# Sheet2.net
KiCad netlist of a schematic drawn in Altium Designer
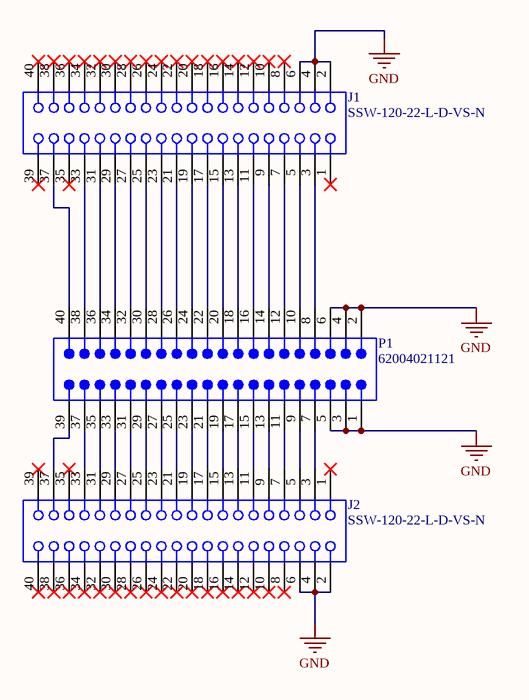
[diagram p0: Sheet2.SchDoc]

(export (version "E")
  (design (tool "Eeschema 10.0.6"))
  (components
    (comp (ref "J1")
      (value "SSW-120-22-L-D-VS-N")
      (footprint "SMTC-SSW-120-22-X-D-VS-N")
      (description "SQ Post Socket, Surface Mount, Vertical, -55 to 125 degC, 2.54 mm Pitch, 40-Pin, Female, RoHS")
      (fields (field (name "MANUFACTURER") "Samtec"))
      (libsource (lib "Altium Content Vault") (part "SMTC-SSW-120-X-X-D"))
    )
    (comp (ref "J2")
      (value "SSW-120-22-L-D-VS-N")
      (footprint "SMTC-SSW-120-22-X-D-VS-N")
      (description "SQ Post Socket, Surface Mount, Vertical, -55 to 125 degC, 2.54 mm Pitch, 40-Pin, Female, RoHS")
      (fields (field (name "MANUFACTURER") "Samtec"))
      (libsource (lib "Altium Content Vault") (part "SMTC-SSW-120-X-X-D"))
    )
    (comp (ref "P1")
      (value "62004021121")
      (footprint "62004021121")
      (description "62004021121 Conn, Header, 40Pos, 2Row, 2Mm Rohs Compliant: Yes")
      (libsource (lib "Altium Content Vault") (part "Header_Male_2R_40P"))
    )
  )
  (nets
    (net (code "1") (name "GND") (class "Default")
      (node (ref "J1") (pin "2") (pinfunction "2_2") (pintype "passive"))
      (node (ref "J1") (pin "4") (pinfunction "4_4") (pintype "passive"))
      (node (ref "J1") (pin "6") (pinfunction "6_6") (pintype "passive"))
      (node (ref "J2") (pin "2") (pinfunction "2_2") (pintype "passive"))
      (node (ref "J2") (pin "4") (pinfunction "4_4") (pintype "passive"))
      (node (ref "J2") (pin "6") (pinfunction "6_6") (pintype "passive"))
      (node (ref "P1") (pin "1") (pinfunction "1_1") (pintype "passive"))
      (node (ref "P1") (pin "2") (pinfunction "2_2") (pintype "passive"))
      (node (ref "P1") (pin "3") (pinfunction "3_3") (pintype "passive"))
      (node (ref "P1") (pin "4") (pinfunction "4_4") (pintype "passive"))
      (node (ref "P1") (pin "5") (pinfunction "5_5") (pintype "passive"))
      (node (ref "P1") (pin "6") (pinfunction "6_6") (pintype "passive"))
    )
    (net (code "2") (name "Net-(J1-Pad3)") (class "Default")
      (node (ref "J1") (pin "3") (pinfunction "3_3") (pintype "passive"))
      (node (ref "P1") (pin "8") (pinfunction "8_8") (pintype "passive"))
    )
    (net (code "3") (name "Net-(J1-Pad5)") (class "Default")
      (node (ref "J1") (pin "5") (pinfunction "5_5") (pintype "passive"))
      (node (ref "P1") (pin "10") (pinfunction "10_10") (pintype "passive"))
    )
    (net (code "4") (name "Net-(J1-Pad7)") (class "Default")
      (node (ref "J1") (pin "7") (pinfunction "7_7") (pintype "passive"))
      (node (ref "P1") (pin "12") (pinfunction "12_12") (pintype "passive"))
    )
    (net (code "5") (name "Net-(J1-Pad9)") (class "Default")
      (node (ref "J1") (pin "9") (pinfunction "9_9") (pintype "passive"))
      (node (ref "P1") (pin "14") (pinfunction "14_14") (pintype "passive"))
    )
    (net (code "6") (name "Net-(J1-Pad11)") (class "Default")
      (node (ref "J1") (pin "11") (pinfunction "11_11") (pintype "passive"))
      (node (ref "P1") (pin "16") (pinfunction "16_16") (pintype "passive"))
    )
    (net (code "7") (name "Net-(J1-Pad13)") (class "Default")
      (node (ref "J1") (pin "13") (pinfunction "13_13") (pintype "passive"))
      (node (ref "P1") (pin "18") (pinfunction "18_18") (pintype "passive"))
    )
    (net (code "8") (name "Net-(J1-Pad15)") (class "Default")
      (node (ref "J1") (pin "15") (pinfunction "15_15") (pintype "passive"))
      (node (ref "P1") (pin "20") (pinfunction "20_20") (pintype "passive"))
    )
    (net (code "9") (name "Net-(J1-Pad17)") (class "Default")
      (node (ref "J1") (pin "17") (pinfunction "17_17") (pintype "passive"))
      (node (ref "P1") (pin "22") (pinfunction "22_22") (pintype "passive"))
    )
    (net (code "10") (name "Net-(J1-Pad19)") (class "Default")
      (node (ref "J1") (pin "19") (pinfunction "19_19") (pintype "passive"))
      (node (ref "P1") (pin "24") (pinfunction "24_24") (pintype "passive"))
    )
    (net (code "11") (name "Net-(J1-Pad21)") (class "Default")
      (node (ref "J1") (pin "21") (pinfunction "21_21") (pintype "passive"))
      (node (ref "P1") (pin "26") (pinfunction "26_26") (pintype "passive"))
    )
    (net (code "12") (name "Net-(J1-Pad23)") (class "Default")
      (node (ref "J1") (pin "23") (pinfunction "23_23") (pintype "passive"))
      (node (ref "P1") (pin "28") (pinfunction "28_28") (pintype "passive"))
    )
    (net (code "13") (name "Net-(J1-Pad25)") (class "Default")
      (node (ref "J1") (pin "25") (pinfunction "25_25") (pintype "passive"))
      (node (ref "P1") (pin "30") (pinfunction "30_30") (pintype "passive"))
    )
    (net (code "14") (name "Net-(J1-Pad27)") (class "Default")
      (node (ref "J1") (pin "27") (pinfunction "27_27") (pintype "passive"))
      (node (ref "P1") (pin "32") (pinfunction "32_32") (pintype "passive"))
    )
    (net (code "15") (name "Net-(J1-Pad29)") (class "Default")
      (node (ref "J1") (pin "29") (pinfunction "29_29") (pintype "passive"))
      (node (ref "P1") (pin "34") (pinfunction "34_34") (pintype "passive"))
    )
    (net (code "16") (name "Net-(J1-Pad31)") (class "Default")
      (node (ref "J1") (pin "31") (pinfunction "31_31") (pintype "passive"))
      (node (ref "P1") (pin "36") (pinfunction "36_36") (pintype "passive"))
    )
    (net (code "17") (name "Net-(J1-Pad33)") (class "Default")
      (node (ref "J1") (pin "33") (pinfunction "33_33") (pintype "passive"))
      (node (ref "P1") (pin "38") (pinfunction "38_38") (pintype "passive"))
    )
    (net (code "18") (name "Net-(J1-Pad37)") (class "Default")
      (node (ref "J1") (pin "37") (pinfunction "37_37") (pintype "passive"))
      (node (ref "P1") (pin "40") (pinfunction "40_40") (pintype "passive"))
    )
    (net (code "19") (name "Net-(J2-Pad3)") (class "Default")
      (node (ref "J2") (pin "3") (pinfunction "3_3") (pintype "passive"))
      (node (ref "P1") (pin "7") (pinfunction "7_7") (pintype "passive"))
    )
    (net (code "20") (name "Net-(J2-Pad5)") (class "Default")
      (node (ref "J2") (pin "5") (pinfunction "5_5") (pintype "passive"))
      (node (ref "P1") (pin "9") (pinfunction "9_9") (pintype "passive"))
    )
    (net (code "21") (name "Net-(J2-Pad7)") (class "Default")
      (node (ref "J2") (pin "7") (pinfunction "7_7") (pintype "passive"))
      (node (ref "P1") (pin "11") (pinfunction "11_11") (pintype "passive"))
    )
    (net (code "22") (name "Net-(J2-Pad9)") (class "Default")
      (node (ref "J2") (pin "9") (pinfunction "9_9") (pintype "passive"))
      (node (ref "P1") (pin "13") (pinfunction "13_13") (pintype "passive"))
    )
    (net (code "23") (name "Net-(J2-Pad11)") (class "Default")
      (node (ref "J2") (pin "11") (pinfunction "11_11") (pintype "passive"))
      (node (ref "P1") (pin "15") (pinfunction "15_15") (pintype "passive"))
    )
    (net (code "24") (name "Net-(J2-Pad13)") (class "Default")
      (node (ref "J2") (pin "13") (pinfunction "13_13") (pintype "passive"))
      (node (ref "P1") (pin "17") (pinfunction "17_17") (pintype "passive"))
    )
    (net (code "25") (name "Net-(J2-Pad15)") (class "Default")
      (node (ref "J2") (pin "15") (pinfunction "15_15") (pintype "passive"))
      (node (ref "P1") (pin "19") (pinfunction "19_19") (pintype "passive"))
    )
    (net (code "26") (name "Net-(J2-Pad17)") (class "Default")
      (node (ref "J2") (pin "17") (pinfunction "17_17") (pintype "passive"))
      (node (ref "P1") (pin "21") (pinfunction "21_21") (pintype "passive"))
    )
    (net (code "27") (name "Net-(J2-Pad19)") (class "Default")
      (node (ref "J2") (pin "19") (pinfunction "19_19") (pintype "passive"))
      (node (ref "P1") (pin "23") (pinfunction "23_23") (pintype "passive"))
    )
    (net (code "28") (name "Net-(J2-Pad21)") (class "Default")
      (node (ref "J2") (pin "21") (pinfunction "21_21") (pintype "passive"))
      (node (ref "P1") (pin "25") (pinfunction "25_25") (pintype "passive"))
    )
    (net (code "29") (name "Net-(J2-Pad23)") (class "Default")
      (node (ref "J2") (pin "23") (pinfunction "23_23") (pintype "passive"))
      (node (ref "P1") (pin "27") (pinfunction "27_27") (pintype "passive"))
    )
    (net (code "30") (name "Net-(J2-Pad25)") (class "Default")
      (node (ref "J2") (pin "25") (pinfunction "25_25") (pintype "passive"))
      (node (ref "P1") (pin "29") (pinfunction "29_29") (pintype "passive"))
    )
    (net (code "31") (name "Net-(J2-Pad27)") (class "Default")
      (node (ref "J2") (pin "27") (pinfunction "27_27") (pintype "passive"))
      (node (ref "P1") (pin "31") (pinfunction "31_31") (pintype "passive"))
    )
    (net (code "32") (name "Net-(J2-Pad29)") (class "Default")
      (node (ref "J2") (pin "29") (pinfunction "29_29") (pintype "passive"))
      (node (ref "P1") (pin "33") (pinfunction "33_33") (pintype "passive"))
    )
    (net (code "33") (name "Net-(J2-Pad31)") (class "Default")
      (node (ref "J2") (pin "31") (pinfunction "31_31") (pintype "passive"))
      (node (ref "P1") (pin "35") (pinfunction "35_35") (pintype "passive"))
    )
    (net (code "34") (name "Net-(J2-Pad33)") (class "Default")
      (node (ref "J2") (pin "33") (pinfunction "33_33") (pintype "passive"))
      (node (ref "P1") (pin "37") (pinfunction "37_37") (pintype "passive"))
    )
    (net (code "35") (name "Net-(J2-Pad37)") (class "Default")
      (node (ref "J2") (pin "37") (pinfunction "37_37") (pintype "passive"))
      (node (ref "P1") (pin "39") (pinfunction "39_39") (pintype "passive"))
    )
    (net (code "36") (name "unconnected-(J1-Pad1)") (class "Default")
      (node (ref "J1") (pin "1") (pinfunction "1_1") (pintype "passive+no_connect"))
    )
    (net (code "37") (name "unconnected-(J1-Pad8)") (class "Default")
      (node (ref "J1") (pin "8") (pinfunction "8_8") (pintype "passive+no_connect"))
    )
    (net (code "38") (name "unconnected-(J1-Pad10)") (class "Default")
      (node (ref "J1") (pin "10") (pinfunction "10_10") (pintype "passive+no_connect"))
    )
    (net (code "39") (name "unconnected-(J1-Pad12)") (class "Default")
      (node (ref "J1") (pin "12") (pinfunction "12_12") (pintype "passive+no_connect"))
    )
    (net (code "40") (name "unconnected-(J1-Pad14)") (class "Default")
      (node (ref "J1") (pin "14") (pinfunction "14_14") (pintype "passive+no_connect"))
    )
    (net (code "41") (name "unconnected-(J1-Pad16)") (class "Default")
      (node (ref "J1") (pin "16") (pinfunction "16_16") (pintype "passive+no_connect"))
    )
    (net (code "42") (name "unconnected-(J1-Pad18)") (class "Default")
      (node (ref "J1") (pin "18") (pinfunction "18_18") (pintype "passive+no_connect"))
    )
    (net (code "43") (name "unconnected-(J1-Pad20)") (class "Default")
      (node (ref "J1") (pin "20") (pinfunction "20_20") (pintype "passive+no_connect"))
    )
    (net (code "44") (name "unconnected-(J1-Pad22)") (class "Default")
      (node (ref "J1") (pin "22") (pinfunction "22_22") (pintype "passive+no_connect"))
    )
    (net (code "45") (name "unconnected-(J1-Pad24)") (class "Default")
      (node (ref "J1") (pin "24") (pinfunction "24_24") (pintype "passive+no_connect"))
    )
    (net (code "46") (name "unconnected-(J1-Pad26)") (class "Default")
      (node (ref "J1") (pin "26") (pinfunction "26_26") (pintype "passive+no_connect"))
    )
    (net (code "47") (name "unconnected-(J1-Pad28)") (class "Default")
      (node (ref "J1") (pin "28") (pinfunction "28_28") (pintype "passive+no_connect"))
    )
    (net (code "48") (name "unconnected-(J1-Pad30)") (class "Default")
      (node (ref "J1") (pin "30") (pinfunction "30_30") (pintype "passive+no_connect"))
    )
    (net (code "49") (name "unconnected-(J1-Pad32)") (class "Default")
      (node (ref "J1") (pin "32") (pinfunction "32_32") (pintype "passive+no_connect"))
    )
    (net (code "50") (name "unconnected-(J1-Pad34)") (class "Default")
      (node (ref "J1") (pin "34") (pinfunction "34_34") (pintype "passive+no_connect"))
    )
    (net (code "51") (name "unconnected-(J1-Pad35)") (class "Default")
      (node (ref "J1") (pin "35") (pinfunction "35_35") (pintype "passive+no_connect"))
    )
    (net (code "52") (name "unconnected-(J1-Pad36)") (class "Default")
      (node (ref "J1") (pin "36") (pinfunction "36_36") (pintype "passive+no_connect"))
    )
    (net (code "53") (name "unconnected-(J1-Pad38)") (class "Default")
      (node (ref "J1") (pin "38") (pinfunction "38_38") (pintype "passive+no_connect"))
    )
    (net (code "54") (name "unconnected-(J1-Pad39)") (class "Default")
      (node (ref "J1") (pin "39") (pinfunction "39_39") (pintype "passive+no_connect"))
    )
    (net (code "55") (name "unconnected-(J1-Pad40)") (class "Default")
      (node (ref "J1") (pin "40") (pinfunction "40_40") (pintype "passive+no_connect"))
    )
    (net (code "56") (name "unconnected-(J2-Pad1)") (class "Default")
      (node (ref "J2") (pin "1") (pinfunction "1_1") (pintype "passive+no_connect"))
    )
    (net (code "57") (name "unconnected-(J2-Pad8)") (class "Default")
      (node (ref "J2") (pin "8") (pinfunction "8_8") (pintype "passive+no_connect"))
    )
    (net (code "58") (name "unconnected-(J2-Pad10)") (class "Default")
      (node (ref "J2") (pin "10") (pinfunction "10_10") (pintype "passive+no_connect"))
    )
    (net (code "59") (name "unconnected-(J2-Pad12)") (class "Default")
      (node (ref "J2") (pin "12") (pinfunction "12_12") (pintype "passive+no_connect"))
    )
    (net (code "60") (name "unconnected-(J2-Pad14)") (class "Default")
      (node (ref "J2") (pin "14") (pinfunction "14_14") (pintype "passive+no_connect"))
    )
    (net (code "61") (name "unconnected-(J2-Pad16)") (class "Default")
      (node (ref "J2") (pin "16") (pinfunction "16_16") (pintype "passive+no_connect"))
    )
    (net (code "62") (name "unconnected-(J2-Pad18)") (class "Default")
      (node (ref "J2") (pin "18") (pinfunction "18_18") (pintype "passive+no_connect"))
    )
    (net (code "63") (name "unconnected-(J2-Pad20)") (class "Default")
      (node (ref "J2") (pin "20") (pinfunction "20_20") (pintype "passive+no_connect"))
    )
    (net (code "64") (name "unconnected-(J2-Pad22)") (class "Default")
      (node (ref "J2") (pin "22") (pinfunction "22_22") (pintype "passive+no_connect"))
    )
    (net (code "65") (name "unconnected-(J2-Pad24)") (class "Default")
      (node (ref "J2") (pin "24") (pinfunction "24_24") (pintype "passive+no_connect"))
    )
    (net (code "66") (name "unconnected-(J2-Pad26)") (class "Default")
      (node (ref "J2") (pin "26") (pinfunction "26_26") (pintype "passive+no_connect"))
    )
    (net (code "67") (name "unconnected-(J2-Pad28)") (class "Default")
      (node (ref "J2") (pin "28") (pinfunction "28_28") (pintype "passive+no_connect"))
    )
    (net (code "68") (name "unconnected-(J2-Pad30)") (class "Default")
      (node (ref "J2") (pin "30") (pinfunction "30_30") (pintype "passive+no_connect"))
    )
    (net (code "69") (name "unconnected-(J2-Pad32)") (class "Default")
      (node (ref "J2") (pin "32") (pinfunction "32_32") (pintype "passive+no_connect"))
    )
    (net (code "70") (name "unconnected-(J2-Pad34)") (class "Default")
      (node (ref "J2") (pin "34") (pinfunction "34_34") (pintype "passive+no_connect"))
    )
    (net (code "71") (name "unconnected-(J2-Pad35)") (class "Default")
      (node (ref "J2") (pin "35") (pinfunction "35_35") (pintype "passive+no_connect"))
    )
    (net (code "72") (name "unconnected-(J2-Pad36)") (class "Default")
      (node (ref "J2") (pin "36") (pinfunction "36_36") (pintype "passive+no_connect"))
    )
    (net (code "73") (name "unconnected-(J2-Pad38)") (class "Default")
      (node (ref "J2") (pin "38") (pinfunction "38_38") (pintype "passive+no_connect"))
    )
    (net (code "74") (name "unconnected-(J2-Pad39)") (class "Default")
      (node (ref "J2") (pin "39") (pinfunction "39_39") (pintype "passive+no_connect"))
    )
    (net (code "75") (name "unconnected-(J2-Pad40)") (class "Default")
      (node (ref "J2") (pin "40") (pinfunction "40_40") (pintype "passive+no_connect"))
    )
  )
)
